# controlo_rev3.net
KiCad netlist of a schematic drawn in Altium Designer
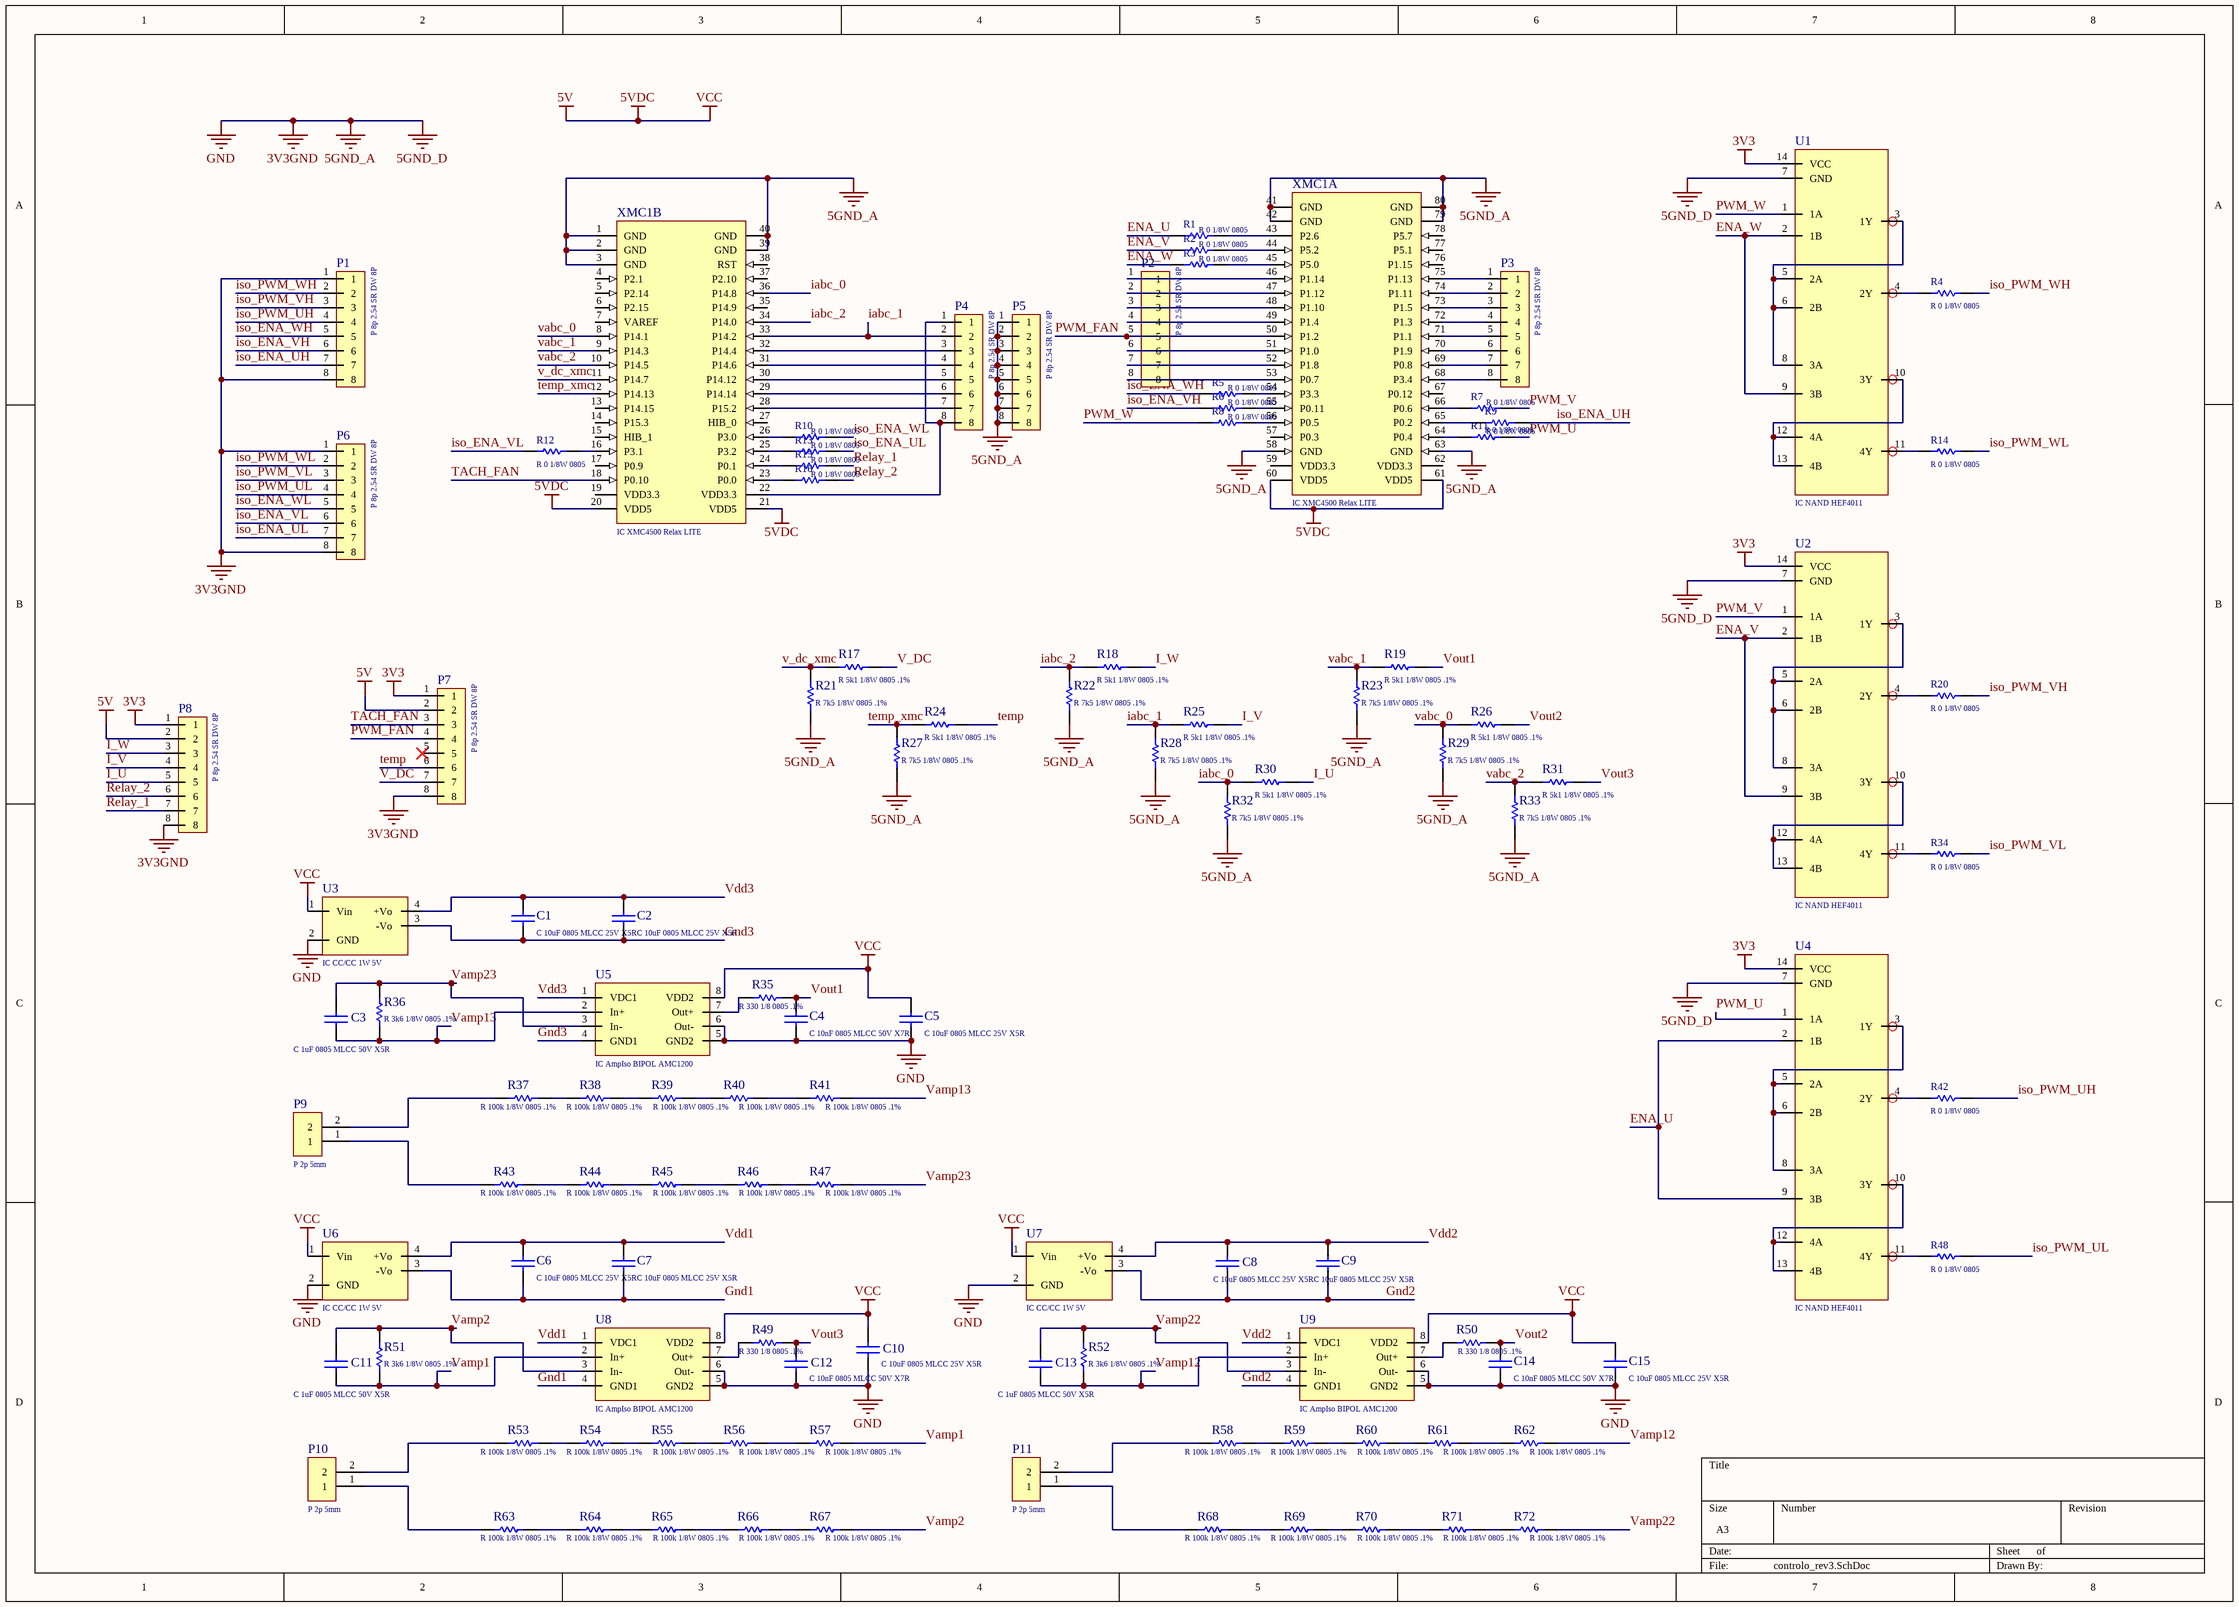
[diagram p0: controlo_rev3.SchDoc]

(export (version "E")
  (design (tool "Eeschema 10.0.6"))
  (components
    (comp (ref "C1")
      (value "C 10uF 0805 MLCC 25V X5R")
      (footprint "CAPC_0805")
      (description "Capacitores de cerâmica multicamada MLCC - SMD/SMT 10uF 25V X5R +/-10% 0805 Gen Purp")
      (libsource (lib "vi_measurement") (part "Capacitor SMD"))
    )
    (comp (ref "C2")
      (value "C 10uF 0805 MLCC 25V X5R")
      (footprint "CAPC_0805")
      (description "Capacitores de cerâmica multicamada MLCC - SMD/SMT 10uF 25V X5R +/-10% 0805 Gen Purp")
      (libsource (lib "vi_measurement") (part "Capacitor SMD"))
    )
    (comp (ref "C3")
      (value "C 1uF 0805 MLCC 50V X5R")
      (footprint "CAPC_0805")
      (description "Capacitores de cerâmica multicamada MLCC - SMD/SMT 0805 50V 1uF 20% X5R")
      (libsource (lib "vi_measurement") (part "Capacitor SMD"))
    )
    (comp (ref "C4")
      (value "C 10nF 0805 MLCC 50V X7R")
      (footprint "CAPC_0805")
      (description "Capacitores de cerâmica multicamada MLCC - SMD/SMT 10nF 50V X7R 10%")
      (libsource (lib "vi_measurement") (part "Capacitor SMD"))
    )
    (comp (ref "C5")
      (value "C 10uF 0805 MLCC 25V X5R")
      (footprint "CAPC_0805")
      (description "Capacitores de cerâmica multicamada MLCC - SMD/SMT 10uF 25V X5R +/-10% 0805 Gen Purp")
      (libsource (lib "vi_measurement") (part "Capacitor SMD"))
    )
    (comp (ref "C6")
      (value "C 10uF 0805 MLCC 25V X5R")
      (footprint "CAPC_0805")
      (description "Capacitores de cerâmica multicamada MLCC - SMD/SMT 10uF 25V X5R +/-10% 0805 Gen Purp")
      (libsource (lib "vi_measurement") (part "Capacitor SMD"))
    )
    (comp (ref "C7")
      (value "C 10uF 0805 MLCC 25V X5R")
      (footprint "CAPC_0805")
      (description "Capacitores de cerâmica multicamada MLCC - SMD/SMT 10uF 25V X5R +/-10% 0805 Gen Purp")
      (libsource (lib "vi_measurement") (part "Capacitor SMD"))
    )
    (comp (ref "C8")
      (value "C 10uF 0805 MLCC 25V X5R")
      (footprint "CAPC_0805")
      (description "Capacitores de cerâmica multicamada MLCC - SMD/SMT 10uF 25V X5R +/-10% 0805 Gen Purp")
      (libsource (lib "vi_measurement") (part "Capacitor SMD"))
    )
    (comp (ref "C9")
      (value "C 10uF 0805 MLCC 25V X5R")
      (footprint "CAPC_0805")
      (description "Capacitores de cerâmica multicamada MLCC - SMD/SMT 10uF 25V X5R +/-10% 0805 Gen Purp")
      (libsource (lib "vi_measurement") (part "Capacitor SMD"))
    )
    (comp (ref "C10")
      (value "C 10uF 0805 MLCC 25V X5R")
      (footprint "CAPC_0805")
      (description "Capacitores de cerâmica multicamada MLCC - SMD/SMT 10uF 25V X5R +/-10% 0805 Gen Purp")
      (libsource (lib "vi_measurement") (part "Capacitor SMD"))
    )
    (comp (ref "C11")
      (value "C 1uF 0805 MLCC 50V X5R")
      (footprint "CAPC_0805")
      (description "Capacitores de cerâmica multicamada MLCC - SMD/SMT 0805 50V 1uF 20% X5R")
      (libsource (lib "vi_measurement") (part "Capacitor SMD"))
    )
    (comp (ref "C12")
      (value "C 10nF 0805 MLCC 50V X7R")
      (footprint "CAPC_0805")
      (description "Capacitores de cerâmica multicamada MLCC - SMD/SMT 10nF 50V X7R 10%")
      (libsource (lib "vi_measurement") (part "Capacitor SMD"))
    )
    (comp (ref "C13")
      (value "C 1uF 0805 MLCC 50V X5R")
      (footprint "CAPC_0805")
      (description "Capacitores de cerâmica multicamada MLCC - SMD/SMT 0805 50V 1uF 20% X5R")
      (libsource (lib "vi_measurement") (part "Capacitor SMD"))
    )
    (comp (ref "C14")
      (value "C 10nF 0805 MLCC 50V X7R")
      (footprint "CAPC_0805")
      (description "Capacitores de cerâmica multicamada MLCC - SMD/SMT 10nF 50V X7R 10%")
      (libsource (lib "vi_measurement") (part "Capacitor SMD"))
    )
    (comp (ref "C15")
      (value "C 10uF 0805 MLCC 25V X5R")
      (footprint "CAPC_0805")
      (description "Capacitores de cerâmica multicamada MLCC - SMD/SMT 10uF 25V X5R +/-10% 0805 Gen Purp")
      (libsource (lib "vi_measurement") (part "Capacitor SMD"))
    )
    (comp (ref "P1")
      (value "P 8p 2.54 SR DW 8P")
      (footprint "Header 8x1 8.5mm")
      (description "Distribuidores e Alojamento de Fios CGrid Hrd SRDW THo le 8ckt")
      (libsource (lib "vmorais_libraries") (part "jumper_8p"))
    )
    (comp (ref "P2")
      (value "P 8p 2.54 SR DW 8P")
      (footprint "Header 8x1 8.5mm")
      (description "Distribuidores e Alojamento de Fios CGrid Hrd SRDW THo le 8ckt")
      (libsource (lib "vmorais_libraries") (part "jumper_8p"))
    )
    (comp (ref "P3")
      (value "P 8p 2.54 SR DW 8P")
      (footprint "Header 8x1 8.5mm")
      (description "Distribuidores e Alojamento de Fios CGrid Hrd SRDW THo le 8ckt")
      (libsource (lib "vmorais_libraries") (part "jumper_8p"))
    )
    (comp (ref "P4")
      (value "P 8p 2.54 SR DW 8P")
      (footprint "Header 8x1 8.5mm")
      (description "Distribuidores e Alojamento de Fios CGrid Hrd SRDW THo le 8ckt")
      (libsource (lib "vmorais_libraries") (part "jumper_8p"))
    )
    (comp (ref "P5")
      (value "P 8p 2.54 SR DW 8P")
      (footprint "Header 8x1 8.5mm")
      (description "Distribuidores e Alojamento de Fios CGrid Hrd SRDW THo le 8ckt")
      (libsource (lib "vmorais_libraries") (part "jumper_8p"))
    )
    (comp (ref "P6")
      (value "P 8p 2.54 SR DW 8P")
      (footprint "Header 8x1 8.5mm")
      (description "Distribuidores e Alojamento de Fios CGrid Hrd SRDW THo le 8ckt")
      (libsource (lib "vmorais_libraries") (part "jumper_8p"))
    )
    (comp (ref "P7")
      (value "P 8p 2.54 SR DW 8P")
      (footprint "Header 8x1 8.5mm")
      (description "Distribuidores e Alojamento de Fios CGrid Hrd SRDW THo le 8ckt")
      (libsource (lib "vmorais_libraries") (part "jumper_8p"))
    )
    (comp (ref "P8")
      (value "P 8p 2.54 SR DW 8P")
      (footprint "Header 8x1 8.5mm")
      (description "Distribuidores e Alojamento de Fios CGrid Hrd SRDW THo le 8ckt")
      (libsource (lib "vmorais_libraries") (part "jumper_8p"))
    )
    (comp (ref "P9")
      (value "P 2p 5mm")
      (footprint "connector1x2_parafuso")
      (description "Bloques de terminales de PCB de perfil estándar RS de 5,0 mm")
      (libsource (lib "malvega_pcb") (part "gen_purpose_conn_1x2"))
    )
    (comp (ref "P10")
      (value "P 2p 5mm")
      (footprint "connector1x2_parafuso")
      (description "Bloques de terminales de PCB de perfil estándar RS de 5,0 mm")
      (libsource (lib "malvega_pcb") (part "gen_purpose_conn_1x2"))
    )
    (comp (ref "P11")
      (value "P 2p 5mm")
      (footprint "connector1x2_parafuso")
      (description "Bloques de terminales de PCB de perfil estándar RS de 5,0 mm")
      (libsource (lib "malvega_pcb") (part "gen_purpose_conn_1x2"))
    )
    (comp (ref "R1")
      (value "R 0 1/8W 0805")
      (footprint "RESC_0805")
      (description "Resistores de Filme Espesso - SMD 1/8Watt 0ohms Commercial Use")
      (libsource (lib "inversor_50a") (part "Resistor"))
    )
    (comp (ref "R2")
      (value "R 0 1/8W 0805")
      (footprint "RESC_0805")
      (description "Resistores de Filme Espesso - SMD 1/8Watt 0ohms Commercial Use")
      (libsource (lib "inversor_50a") (part "Resistor"))
    )
    (comp (ref "R3")
      (value "R 0 1/8W 0805")
      (footprint "RESC_0805")
      (description "Resistores de Filme Espesso - SMD 1/8Watt 0ohms Commercial Use")
      (libsource (lib "inversor_50a") (part "Resistor"))
    )
    (comp (ref "R4")
      (value "R 0 1/8W 0805")
      (footprint "RESC_0805")
      (description "Resistores de Filme Espesso - SMD 1/8Watt 0ohms Commercial Use")
      (libsource (lib "inversor_50a") (part "Resistor"))
    )
    (comp (ref "R5")
      (value "R 0 1/8W 0805")
      (footprint "RESC_0805")
      (description "Resistores de Filme Espesso - SMD 1/8Watt 0ohms Commercial Use")
      (libsource (lib "inversor_50a") (part "Resistor"))
    )
    (comp (ref "R6")
      (value "R 0 1/8W 0805")
      (footprint "RESC_0805")
      (description "Resistores de Filme Espesso - SMD 1/8Watt 0ohms Commercial Use")
      (libsource (lib "inversor_50a") (part "Resistor"))
    )
    (comp (ref "R7")
      (value "R 0 1/8W 0805")
      (footprint "RESC_0805")
      (description "Resistores de Filme Espesso - SMD 1/8Watt 0ohms Commercial Use")
      (libsource (lib "inversor_50a") (part "Resistor"))
    )
    (comp (ref "R8")
      (value "R 0 1/8W 0805")
      (footprint "RESC_0805")
      (description "Resistores de Filme Espesso - SMD 1/8Watt 0ohms Commercial Use")
      (libsource (lib "inversor_50a") (part "Resistor"))
    )
    (comp (ref "R9")
      (value "R 0 1/8W 0805")
      (footprint "RESC_0805")
      (description "Resistores de Filme Espesso - SMD 1/8Watt 0ohms Commercial Use")
      (libsource (lib "inversor_50a") (part "Resistor"))
    )
    (comp (ref "R10")
      (value "R 0 1/8W 0805")
      (footprint "RESC_0805")
      (description "Resistores de Filme Espesso - SMD 1/8Watt 0ohms Commercial Use")
      (libsource (lib "inversor_50a") (part "Resistor"))
    )
    (comp (ref "R11")
      (value "R 0 1/8W 0805")
      (footprint "RESC_0805")
      (description "Resistores de Filme Espesso - SMD 1/8Watt 0ohms Commercial Use")
      (libsource (lib "inversor_50a") (part "Resistor"))
    )
    (comp (ref "R12")
      (value "R 0 1/8W 0805")
      (footprint "RESC_0805")
      (description "Resistores de Filme Espesso - SMD 1/8Watt 0ohms Commercial Use")
      (libsource (lib "inversor_50a") (part "Resistor"))
    )
    (comp (ref "R13")
      (value "R 0 1/8W 0805")
      (footprint "RESC_0805")
      (description "Resistores de Filme Espesso - SMD 1/8Watt 0ohms Commercial Use")
      (libsource (lib "inversor_50a") (part "Resistor"))
    )
    (comp (ref "R14")
      (value "R 0 1/8W 0805")
      (footprint "RESC_0805")
      (description "Resistores de Filme Espesso - SMD 1/8Watt 0ohms Commercial Use")
      (libsource (lib "inversor_50a") (part "Resistor"))
    )
    (comp (ref "R15")
      (value "R 0 1/8W 0805")
      (footprint "RESC_0805")
      (description "Resistores de Filme Espesso - SMD 1/8Watt 0ohms Commercial Use")
      (libsource (lib "inversor_50a") (part "Resistor"))
    )
    (comp (ref "R16")
      (value "R 0 1/8W 0805")
      (footprint "RESC_0805")
      (description "Resistores de Filme Espesso - SMD 1/8Watt 0ohms Commercial Use")
      (libsource (lib "inversor_50a") (part "Resistor"))
    )
    (comp (ref "R17")
      (value "R 5k1 1/8W 0805 .1%")
      (footprint "RESC_0805")
      (description "Resistores de Filme Fino - SMD 0805 5.1Kohm 1/8W .1% 25ppm")
      (libsource (lib "inversor_50a") (part "Resistor"))
    )
    (comp (ref "R18")
      (value "R 5k1 1/8W 0805 .1%")
      (footprint "RESC_0805")
      (description "Resistores de Filme Fino - SMD 0805 5.1Kohm 1/8W .1% 25ppm")
      (libsource (lib "inversor_50a") (part "Resistor"))
    )
    (comp (ref "R19")
      (value "R 5k1 1/8W 0805 .1%")
      (footprint "RESC_0805")
      (description "Resistores de Filme Fino - SMD 0805 5.1Kohm 1/8W .1% 25ppm")
      (libsource (lib "inversor_50a") (part "Resistor"))
    )
    (comp (ref "R20")
      (value "R 0 1/8W 0805")
      (footprint "RESC_0805")
      (description "Resistores de Filme Espesso - SMD 1/8Watt 0ohms Commercial Use")
      (libsource (lib "inversor_50a") (part "Resistor"))
    )
    (comp (ref "R21")
      (value "R 7k5 1/8W 0805 .1%")
      (footprint "RESC_0805")
      (description "Resistores de Filme Fino - SMD 7.5K OHM .1% 25ppm")
      (libsource (lib "inversor_50a") (part "Resistor"))
    )
    (comp (ref "R22")
      (value "R 7k5 1/8W 0805 .1%")
      (footprint "RESC_0805")
      (description "Resistores de Filme Fino - SMD 7.5K OHM .1% 25ppm")
      (libsource (lib "inversor_50a") (part "Resistor"))
    )
    (comp (ref "R23")
      (value "R 7k5 1/8W 0805 .1%")
      (footprint "RESC_0805")
      (description "Resistores de Filme Fino - SMD 7.5K OHM .1% 25ppm")
      (libsource (lib "inversor_50a") (part "Resistor"))
    )
    (comp (ref "R24")
      (value "R 5k1 1/8W 0805 .1%")
      (footprint "RESC_0805")
      (description "Resistores de Filme Fino - SMD 0805 5.1Kohm 1/8W .1% 25ppm")
      (libsource (lib "inversor_50a") (part "Resistor"))
    )
    (comp (ref "R25")
      (value "R 5k1 1/8W 0805 .1%")
      (footprint "RESC_0805")
      (description "Resistores de Filme Fino - SMD 0805 5.1Kohm 1/8W .1% 25ppm")
      (libsource (lib "inversor_50a") (part "Resistor"))
    )
    (comp (ref "R26")
      (value "R 5k1 1/8W 0805 .1%")
      (footprint "RESC_0805")
      (description "Resistores de Filme Fino - SMD 0805 5.1Kohm 1/8W .1% 25ppm")
      (libsource (lib "inversor_50a") (part "Resistor"))
    )
    (comp (ref "R27")
      (value "R 7k5 1/8W 0805 .1%")
      (footprint "RESC_0805")
      (description "Resistores de Filme Fino - SMD 7.5K OHM .1% 25ppm")
      (libsource (lib "inversor_50a") (part "Resistor"))
    )
    (comp (ref "R28")
      (value "R 7k5 1/8W 0805 .1%")
      (footprint "RESC_0805")
      (description "Resistores de Filme Fino - SMD 7.5K OHM .1% 25ppm")
      (libsource (lib "inversor_50a") (part "Resistor"))
    )
    (comp (ref "R29")
      (value "R 7k5 1/8W 0805 .1%")
      (footprint "RESC_0805")
      (description "Resistores de Filme Fino - SMD 7.5K OHM .1% 25ppm")
      (libsource (lib "inversor_50a") (part "Resistor"))
    )
    (comp (ref "R30")
      (value "R 5k1 1/8W 0805 .1%")
      (footprint "RESC_0805")
      (description "Resistores de Filme Fino - SMD 0805 5.1Kohm 1/8W .1% 25ppm")
      (libsource (lib "inversor_50a") (part "Resistor"))
    )
    (comp (ref "R31")
      (value "R 5k1 1/8W 0805 .1%")
      (footprint "RESC_0805")
      (description "Resistores de Filme Fino - SMD 0805 5.1Kohm 1/8W .1% 25ppm")
      (libsource (lib "inversor_50a") (part "Resistor"))
    )
    (comp (ref "R32")
      (value "R 7k5 1/8W 0805 .1%")
      (footprint "RESC_0805")
      (description "Resistores de Filme Fino - SMD 7.5K OHM .1% 25ppm")
      (libsource (lib "inversor_50a") (part "Resistor"))
    )
    (comp (ref "R33")
      (value "R 7k5 1/8W 0805 .1%")
      (footprint "RESC_0805")
      (description "Resistores de Filme Fino - SMD 7.5K OHM .1% 25ppm")
      (libsource (lib "inversor_50a") (part "Resistor"))
    )
    (comp (ref "R34")
      (value "R 0 1/8W 0805")
      (footprint "RESC_0805")
      (description "Resistores de Filme Espesso - SMD 1/8Watt 0ohms Commercial Use")
      (libsource (lib "inversor_50a") (part "Resistor"))
    )
    (comp (ref "R35")
      (value "R 330 1/8 0805 .1%")
      (footprint "RESC_0805")
      (description "Resistores de Filme Fino - SMD CPF 0805 330R 0.1% 25PPM 1K RL")
      (libsource (lib "inversor_50a") (part "Resistor"))
    )
    (comp (ref "R36")
      (value "R 3k6 1/8W 0805 .1%")
      (footprint "RESC_0805")
      (description "Resistores de Filme Fino - SMD 1/8W 3.6K ohm .1% 25ppm")
      (libsource (lib "inversor_50a") (part "Resistor"))
    )
    (comp (ref "R37")
      (value "R 100k 1/8W 0805 .1%")
      (footprint "RESC_0805")
      (description "Resistores de Filme Fino - SMD 100 Kohm .1% 0805 25PPM")
      (libsource (lib "inversor_50a") (part "Resistor"))
    )
    (comp (ref "R38")
      (value "R 100k 1/8W 0805 .1%")
      (footprint "RESC_0805")
      (description "Resistores de Filme Fino - SMD 100 Kohm .1% 0805 25PPM")
      (libsource (lib "inversor_50a") (part "Resistor"))
    )
    (comp (ref "R39")
      (value "R 100k 1/8W 0805 .1%")
      (footprint "RESC_0805")
      (description "Resistores de Filme Fino - SMD 100 Kohm .1% 0805 25PPM")
      (libsource (lib "inversor_50a") (part "Resistor"))
    )
    (comp (ref "R40")
      (value "R 100k 1/8W 0805 .1%")
      (footprint "RESC_0805")
      (description "Resistores de Filme Fino - SMD 100 Kohm .1% 0805 25PPM")
      (libsource (lib "inversor_50a") (part "Resistor"))
    )
    (comp (ref "R41")
      (value "R 100k 1/8W 0805 .1%")
      (footprint "RESC_0805")
      (description "Resistores de Filme Fino - SMD 100 Kohm .1% 0805 25PPM")
      (libsource (lib "inversor_50a") (part "Resistor"))
    )
    (comp (ref "R42")
      (value "R 0 1/8W 0805")
      (footprint "RESC_0805")
      (description "Resistores de Filme Espesso - SMD 1/8Watt 0ohms Commercial Use")
      (libsource (lib "inversor_50a") (part "Resistor"))
    )
    (comp (ref "R43")
      (value "R 100k 1/8W 0805 .1%")
      (footprint "RESC_0805")
      (description "Resistores de Filme Fino - SMD 100 Kohm .1% 0805 25PPM")
      (libsource (lib "inversor_50a") (part "Resistor"))
    )
    (comp (ref "R44")
      (value "R 100k 1/8W 0805 .1%")
      (footprint "RESC_0805")
      (description "Resistores de Filme Fino - SMD 100 Kohm .1% 0805 25PPM")
      (libsource (lib "inversor_50a") (part "Resistor"))
    )
    (comp (ref "R45")
      (value "R 100k 1/8W 0805 .1%")
      (footprint "RESC_0805")
      (description "Resistores de Filme Fino - SMD 100 Kohm .1% 0805 25PPM")
      (libsource (lib "inversor_50a") (part "Resistor"))
    )
    (comp (ref "R46")
      (value "R 100k 1/8W 0805 .1%")
      (footprint "RESC_0805")
      (description "Resistores de Filme Fino - SMD 100 Kohm .1% 0805 25PPM")
      (libsource (lib "inversor_50a") (part "Resistor"))
    )
    (comp (ref "R47")
      (value "R 100k 1/8W 0805 .1%")
      (footprint "RESC_0805")
      (description "Resistores de Filme Fino - SMD 100 Kohm .1% 0805 25PPM")
      (libsource (lib "inversor_50a") (part "Resistor"))
    )
    (comp (ref "R48")
      (value "R 0 1/8W 0805")
      (footprint "RESC_0805")
      (description "Resistores de Filme Espesso - SMD 1/8Watt 0ohms Commercial Use")
      (libsource (lib "inversor_50a") (part "Resistor"))
    )
    (comp (ref "R49")
      (value "R 330 1/8 0805 .1%")
      (footprint "RESC_0805")
      (description "Resistores de Filme Fino - SMD CPF 0805 330R 0.1% 25PPM 1K RL")
      (libsource (lib "inversor_50a") (part "Resistor"))
    )
    (comp (ref "R50")
      (value "R 330 1/8 0805 .1%")
      (footprint "RESC_0805")
      (description "Resistores de Filme Fino - SMD CPF 0805 330R 0.1% 25PPM 1K RL")
      (libsource (lib "inversor_50a") (part "Resistor"))
    )
    (comp (ref "R51")
      (value "R 3k6 1/8W 0805 .1%")
      (footprint "RESC_0805")
      (description "Resistores de Filme Fino - SMD 1/8W 3.6K ohm .1% 25ppm")
      (libsource (lib "inversor_50a") (part "Resistor"))
    )
    (comp (ref "R52")
      (value "R 3k6 1/8W 0805 .1%")
      (footprint "RESC_0805")
      (description "Resistores de Filme Fino - SMD 1/8W 3.6K ohm .1% 25ppm")
      (libsource (lib "inversor_50a") (part "Resistor"))
    )
    (comp (ref "R53")
      (value "R 100k 1/8W 0805 .1%")
      (footprint "RESC_0805")
      (description "Resistores de Filme Fino - SMD 100 Kohm .1% 0805 25PPM")
      (libsource (lib "inversor_50a") (part "Resistor"))
    )
    (comp (ref "R54")
      (value "R 100k 1/8W 0805 .1%")
      (footprint "RESC_0805")
      (description "Resistores de Filme Fino - SMD 100 Kohm .1% 0805 25PPM")
      (libsource (lib "inversor_50a") (part "Resistor"))
    )
    (comp (ref "R55")
      (value "R 100k 1/8W 0805 .1%")
      (footprint "RESC_0805")
      (description "Resistores de Filme Fino - SMD 100 Kohm .1% 0805 25PPM")
      (libsource (lib "inversor_50a") (part "Resistor"))
    )
    (comp (ref "R56")
      (value "R 100k 1/8W 0805 .1%")
      (footprint "RESC_0805")
      (description "Resistores de Filme Fino - SMD 100 Kohm .1% 0805 25PPM")
      (libsource (lib "inversor_50a") (part "Resistor"))
    )
    (comp (ref "R57")
      (value "R 100k 1/8W 0805 .1%")
      (footprint "RESC_0805")
      (description "Resistores de Filme Fino - SMD 100 Kohm .1% 0805 25PPM")
      (libsource (lib "inversor_50a") (part "Resistor"))
    )
    (comp (ref "R58")
      (value "R 100k 1/8W 0805 .1%")
      (footprint "RESC_0805")
      (description "Resistores de Filme Fino - SMD 100 Kohm .1% 0805 25PPM")
      (libsource (lib "inversor_50a") (part "Resistor"))
    )
    (comp (ref "R59")
      (value "R 100k 1/8W 0805 .1%")
      (footprint "RESC_0805")
      (description "Resistores de Filme Fino - SMD 100 Kohm .1% 0805 25PPM")
      (libsource (lib "inversor_50a") (part "Resistor"))
    )
    (comp (ref "R60")
      (value "R 100k 1/8W 0805 .1%")
      (footprint "RESC_0805")
      (description "Resistores de Filme Fino - SMD 100 Kohm .1% 0805 25PPM")
      (libsource (lib "inversor_50a") (part "Resistor"))
    )
    (comp (ref "R61")
      (value "R 100k 1/8W 0805 .1%")
      (footprint "RESC_0805")
      (description "Resistores de Filme Fino - SMD 100 Kohm .1% 0805 25PPM")
      (libsource (lib "inversor_50a") (part "Resistor"))
    )
    (comp (ref "R62")
      (value "R 100k 1/8W 0805 .1%")
      (footprint "RESC_0805")
      (description "Resistores de Filme Fino - SMD 100 Kohm .1% 0805 25PPM")
      (libsource (lib "inversor_50a") (part "Resistor"))
    )
    (comp (ref "R63")
      (value "R 100k 1/8W 0805 .1%")
      (footprint "RESC_0805")
      (description "Resistores de Filme Fino - SMD 100 Kohm .1% 0805 25PPM")
      (libsource (lib "inversor_50a") (part "Resistor"))
    )
    (comp (ref "R64")
      (value "R 100k 1/8W 0805 .1%")
      (footprint "RESC_0805")
      (description "Resistores de Filme Fino - SMD 100 Kohm .1% 0805 25PPM")
      (libsource (lib "inversor_50a") (part "Resistor"))
    )
    (comp (ref "R65")
      (value "R 100k 1/8W 0805 .1%")
      (footprint "RESC_0805")
      (description "Resistores de Filme Fino - SMD 100 Kohm .1% 0805 25PPM")
      (libsource (lib "inversor_50a") (part "Resistor"))
    )
    (comp (ref "R66")
      (value "R 100k 1/8W 0805 .1%")
      (footprint "RESC_0805")
      (description "Resistores de Filme Fino - SMD 100 Kohm .1% 0805 25PPM")
      (libsource (lib "inversor_50a") (part "Resistor"))
    )
    (comp (ref "R67")
      (value "R 100k 1/8W 0805 .1%")
      (footprint "RESC_0805")
      (description "Resistores de Filme Fino - SMD 100 Kohm .1% 0805 25PPM")
      (libsource (lib "inversor_50a") (part "Resistor"))
    )
    (comp (ref "R68")
      (value "R 100k 1/8W 0805 .1%")
      (footprint "RESC_0805")
      (description "Resistores de Filme Fino - SMD 100 Kohm .1% 0805 25PPM")
      (libsource (lib "inversor_50a") (part "Resistor"))
    )
    (comp (ref "R69")
      (value "R 100k 1/8W 0805 .1%")
      (footprint "RESC_0805")
      (description "Resistores de Filme Fino - SMD 100 Kohm .1% 0805 25PPM")
      (libsource (lib "inversor_50a") (part "Resistor"))
    )
    (comp (ref "R70")
      (value "R 100k 1/8W 0805 .1%")
      (footprint "RESC_0805")
      (description "Resistores de Filme Fino - SMD 100 Kohm .1% 0805 25PPM")
      (libsource (lib "inversor_50a") (part "Resistor"))
    )
    (comp (ref "R71")
      (value "R 100k 1/8W 0805 .1%")
      (footprint "RESC_0805")
      (description "Resistores de Filme Fino - SMD 100 Kohm .1% 0805 25PPM")
      (libsource (lib "inversor_50a") (part "Resistor"))
    )
    (comp (ref "R72")
      (value "R 100k 1/8W 0805 .1%")
      (footprint "RESC_0805")
      (description "Resistores de Filme Fino - SMD 100 Kohm .1% 0805 25PPM")
      (libsource (lib "inversor_50a") (part "Resistor"))
    )
    (comp (ref "U1")
      (value "IC NAND HEF4011")
      (footprint "SOIC-14N")
      (description "Portas lógicas QUADRUPLE 2-INPUT NAND GATE")
      (libsource (lib "vmorais_libraries") (part "HEF4011"))
    )
    (comp (ref "U2")
      (value "IC NAND HEF4011")
      (footprint "SOIC-14N")
      (description "Portas lógicas QUADRUPLE 2-INPUT NAND GATE")
      (libsource (lib "vmorais_libraries") (part "HEF4011"))
    )
    (comp (ref "U3")
      (value "IC CC/CC 1W 5V")
      (footprint "DC/DC_ISO")
      (description "Conversores CC/CC com isolação 1W 5Vin 5Vout 200mA SIP7")
      (libsource (lib "vi_measurement") (part "DC/DC_ISO"))
    )
    (comp (ref "U4")
      (value "IC NAND HEF4011")
      (footprint "SOIC-14N")
      (description "Portas lógicas QUADRUPLE 2-INPUT NAND GATE")
      (libsource (lib "vmorais_libraries") (part "HEF4011"))
    )
    (comp (ref "U5")
      (value "IC AmpIso BIPOL AMC1200")
      (footprint "SOIC8")
      (description "Amplificadores de isolamento 4kV peak Iso Amp")
      (libsource (lib "vi_measurement") (part "AMC1200"))
    )
    (comp (ref "U6")
      (value "IC CC/CC 1W 5V")
      (footprint "DC/DC_ISO")
      (description "Conversores CC/CC com isolação 1W 5Vin 5Vout 200mA SIP7")
      (libsource (lib "vi_measurement") (part "DC/DC_ISO"))
    )
    (comp (ref "U7")
      (value "IC CC/CC 1W 5V")
      (footprint "DC/DC_ISO")
      (description "Conversores CC/CC com isolação 1W 5Vin 5Vout 200mA SIP7")
      (libsource (lib "vi_measurement") (part "DC/DC_ISO"))
    )
    (comp (ref "U8")
      (value "IC AmpIso BIPOL AMC1200")
      (footprint "SOIC8")
      (description "Amplificadores de isolamento 4kV peak Iso Amp")
      (libsource (lib "vi_measurement") (part "AMC1200"))
    )
    (comp (ref "U9")
      (value "IC AmpIso BIPOL AMC1200")
      (footprint "SOIC8")
      (description "Amplificadores de isolamento 4kV peak Iso Amp")
      (libsource (lib "vi_measurement") (part "AMC1200"))
    )
    (comp (ref "XMC1")
      (value "IC XMC4500 Relax LITE")
      (footprint "XMC4500")
      (libsource (lib "vmorais_libraries") (part "XMC4500"))
    )
  )
  (nets
    (net (code "1") (name "/ENA_U") (class "Default")
      (node (ref "R1") (pin "1") (pinfunction "1_1") (pintype "passive"))
      (node (ref "U4") (pin "2") (pinfunction "1B_2") (pintype "passive"))
      (node (ref "U4") (pin "9") (pinfunction "3B_9") (pintype "passive"))
    )
    (net (code "2") (name "/ENA_V") (class "Default")
      (node (ref "R2") (pin "1") (pinfunction "1_1") (pintype "passive"))
      (node (ref "U2") (pin "2") (pinfunction "1B_2") (pintype "passive"))
      (node (ref "U2") (pin "9") (pinfunction "3B_9") (pintype "passive"))
    )
    (net (code "3") (name "/ENA_W") (class "Default")
      (node (ref "R3") (pin "1") (pinfunction "1_1") (pintype "passive"))
      (node (ref "U1") (pin "2") (pinfunction "1B_2") (pintype "passive"))
      (node (ref "U1") (pin "9") (pinfunction "3B_9") (pintype "passive"))
    )
    (net (code "4") (name "/Gnd1") (class "Default")
      (node (ref "C6") (pin "1") (pinfunction "1_1") (pintype "passive"))
      (node (ref "C7") (pin "1") (pinfunction "1_1") (pintype "passive"))
      (node (ref "U6") (pin "3") (pinfunction "-Vo_3") (pintype "passive"))
      (node (ref "U8") (pin "4") (pinfunction "GND1_4") (pintype "passive"))
    )
    (net (code "5") (name "/Gnd2") (class "Default")
      (node (ref "C8") (pin "1") (pinfunction "1_1") (pintype "passive"))
      (node (ref "C9") (pin "1") (pinfunction "1_1") (pintype "passive"))
      (node (ref "U7") (pin "3") (pinfunction "-Vo_3") (pintype "passive"))
      (node (ref "U9") (pin "4") (pinfunction "GND1_4") (pintype "passive"))
    )
    (net (code "6") (name "/Gnd3") (class "Default")
      (node (ref "C1") (pin "1") (pinfunction "1_1") (pintype "passive"))
      (node (ref "C2") (pin "1") (pinfunction "1_1") (pintype "passive"))
      (node (ref "U3") (pin "3") (pinfunction "-Vo_3") (pintype "passive"))
      (node (ref "U5") (pin "4") (pinfunction "GND1_4") (pintype "passive"))
    )
    (net (code "7") (name "/I_U") (class "Default")
      (node (ref "P8") (pin "5") (pinfunction "5_5") (pintype "passive"))
      (node (ref "R30") (pin "2") (pinfunction "2_2") (pintype "passive"))
    )
    (net (code "8") (name "/I_V") (class "Default")
      (node (ref "P8") (pin "4") (pinfunction "4_4") (pintype "passive"))
      (node (ref "R25") (pin "2") (pinfunction "2_2") (pintype "passive"))
    )
    (net (code "9") (name "/I_W") (class "Default")
      (node (ref "P8") (pin "3") (pinfunction "3_3") (pintype "passive"))
      (node (ref "R18") (pin "2") (pinfunction "2_2") (pintype "passive"))
    )
    (net (code "10") (name "/PWM_FAN") (class "Default")
      (node (ref "P2") (pin "5") (pinfunction "5_5") (pintype "passive"))
      (node (ref "P7") (pin "4") (pinfunction "4_4") (pintype "passive"))
      (node (ref "XMC1") (pin "50") (pinfunction "P1.2_50") (pintype "input"))
    )
    (net (code "11") (name "/PWM_U") (class "Default")
      (node (ref "R11") (pin "2") (pinfunction "2_2") (pintype "passive"))
      (node (ref "U4") (pin "1") (pinfunction "1A_1") (pintype "passive"))
    )
    (net (code "12") (name "/PWM_V") (class "Default")
      (node (ref "R7") (pin "2") (pinfunction "2_2") (pintype "passive"))
      (node (ref "U2") (pin "1") (pinfunction "1A_1") (pintype "passive"))
    )
    (net (code "13") (name "/PWM_W") (class "Default")
      (node (ref "R8") (pin "1") (pinfunction "1_1") (pintype "passive"))
      (node (ref "U1") (pin "1") (pinfunction "1A_1") (pintype "passive"))
    )
    (net (code "14") (name "/Relay_1") (class "Default")
      (node (ref "P8") (pin "7") (pinfunction "7_7") (pintype "passive"))
      (node (ref "R15") (pin "2") (pinfunction "2_2") (pintype "passive"))
    )
    (net (code "15") (name "/Relay_2") (class "Default")
      (node (ref "P8") (pin "6") (pinfunction "6_6") (pintype "passive"))
      (node (ref "R16") (pin "2") (pinfunction "2_2") (pintype "passive"))
    )
    (net (code "16") (name "/TACH_FAN") (class "Default")
      (node (ref "P7") (pin "3") (pinfunction "3_3") (pintype "passive"))
      (node (ref "XMC1") (pin "18") (pinfunction "P0.10_18") (pintype "input"))
    )
    (net (code "17") (name "/V_DC") (class "Default")
      (node (ref "P7") (pin "7") (pinfunction "7_7") (pintype "passive"))
      (node (ref "R17") (pin "2") (pinfunction "2_2") (pintype "passive"))
    )
    (net (code "18") (name "/Vamp1") (class "Default")
      (node (ref "C11") (pin "1") (pinfunction "1_1") (pintype "passive"))
      (node (ref "R51") (pin "1") (pinfunction "1_1") (pintype "passive"))
      (node (ref "R57") (pin "2") (pinfunction "2_2") (pintype "passive"))
      (node (ref "U8") (pin "2") (pinfunction "In+_2") (pintype "passive"))
    )
    (net (code "19") (name "/Vamp2") (class "Default")
      (node (ref "C11") (pin "2") (pinfunction "2_2") (pintype "passive"))
      (node (ref "R51") (pin "2") (pinfunction "2_2") (pintype "passive"))
      (node (ref "R67") (pin "2") (pinfunction "2_2") (pintype "passive"))
      (node (ref "U8") (pin "3") (pinfunction "In-_3") (pintype "passive"))
    )
    (net (code "20") (name "/Vamp12") (class "Default")
      (node (ref "C13") (pin "1") (pinfunction "1_1") (pintype "passive"))
      (node (ref "R52") (pin "1") (pinfunction "1_1") (pintype "passive"))
      (node (ref "R62") (pin "2") (pinfunction "2_2") (pintype "passive"))
      (node (ref "U9") (pin "2") (pinfunction "In+_2") (pintype "passive"))
    )
    (net (code "21") (name "/Vamp13") (class "Default")
      (node (ref "C3") (pin "1") (pinfunction "1_1") (pintype "passive"))
      (node (ref "R36") (pin "1") (pinfunction "1_1") (pintype "passive"))
      (node (ref "R41") (pin "2") (pinfunction "2_2") (pintype "passive"))
      (node (ref "U5") (pin "2") (pinfunction "In+_2") (pintype "passive"))
    )
    (net (code "22") (name "/Vamp22") (class "Default")
      (node (ref "C13") (pin "2") (pinfunction "2_2") (pintype "passive"))
      (node (ref "R52") (pin "2") (pinfunction "2_2") (pintype "passive"))
      (node (ref "R72") (pin "2") (pinfunction "2_2") (pintype "passive"))
      (node (ref "U9") (pin "3") (pinfunction "In-_3") (pintype "passive"))
    )
    (net (code "23") (name "/Vamp23") (class "Default")
      (node (ref "C3") (pin "2") (pinfunction "2_2") (pintype "passive"))
      (node (ref "R36") (pin "2") (pinfunction "2_2") (pintype "passive"))
      (node (ref "R47") (pin "2") (pinfunction "2_2") (pintype "passive"))
      (node (ref "U5") (pin "3") (pinfunction "In-_3") (pintype "passive"))
    )
    (net (code "24") (name "/Vdd1") (class "Default")
      (node (ref "C6") (pin "2") (pinfunction "2_2") (pintype "passive"))
      (node (ref "C7") (pin "2") (pinfunction "2_2") (pintype "passive"))
      (node (ref "U6") (pin "4") (pinfunction "+Vo_4") (pintype "passive"))
      (node (ref "U8") (pin "1") (pinfunction "VDC1_1") (pintype "passive"))
    )
    (net (code "25") (name "/Vdd2") (class "Default")
      (node (ref "C8") (pin "2") (pinfunction "2_2") (pintype "passive"))
      (node (ref "C9") (pin "2") (pinfunction "2_2") (pintype "passive"))
      (node (ref "U7") (pin "4") (pinfunction "+Vo_4") (pintype "passive"))
      (node (ref "U9") (pin "1") (pinfunction "VDC1_1") (pintype "passive"))
    )
    (net (code "26") (name "/Vdd3") (class "Default")
      (node (ref "C1") (pin "2") (pinfunction "2_2") (pintype "passive"))
      (node (ref "C2") (pin "2") (pinfunction "2_2") (pintype "passive"))
      (node (ref "U3") (pin "4") (pinfunction "+Vo_4") (pintype "passive"))
      (node (ref "U5") (pin "1") (pinfunction "VDC1_1") (pintype "passive"))
    )
    (net (code "27") (name "/Vout1") (class "Default")
      (node (ref "C4") (pin "2") (pinfunction "2_2") (pintype "passive"))
      (node (ref "R19") (pin "2") (pinfunction "2_2") (pintype "passive"))
      (node (ref "R35") (pin "2") (pinfunction "2_2") (pintype "passive"))
    )
    (net (code "28") (name "/Vout2") (class "Default")
      (node (ref "C14") (pin "2") (pinfunction "2_2") (pintype "passive"))
      (node (ref "R26") (pin "2") (pinfunction "2_2") (pintype "passive"))
      (node (ref "R50") (pin "2") (pinfunction "2_2") (pintype "passive"))
    )
    (net (code "29") (name "/Vout3") (class "Default")
      (node (ref "C12") (pin "2") (pinfunction "2_2") (pintype "passive"))
      (node (ref "R31") (pin "2") (pinfunction "2_2") (pintype "passive"))
      (node (ref "R49") (pin "2") (pinfunction "2_2") (pintype "passive"))
    )
    (net (code "30") (name "/iabc_0") (class "Default")
      (node (ref "R30") (pin "1") (pinfunction "1_1") (pintype "passive"))
      (node (ref "R32") (pin "2") (pinfunction "2_2") (pintype "passive"))
      (node (ref "XMC1") (pin "36") (pinfunction "P14.8_36") (pintype "input"))
    )
    (net (code "31") (name "/iabc_1") (class "Default")
      (node (ref "P4") (pin "2") (pinfunction "2_2") (pintype "passive"))
      (node (ref "R25") (pin "1") (pinfunction "1_1") (pintype "passive"))
      (node (ref "R28") (pin "2") (pinfunction "2_2") (pintype "passive"))
      (node (ref "XMC1") (pin "33") (pinfunction "P14.2_33") (pintype "input"))
    )
    (net (code "32") (name "/iabc_2") (class "Default")
      (node (ref "R18") (pin "1") (pinfunction "1_1") (pintype "passive"))
      (node (ref "R22") (pin "2") (pinfunction "2_2") (pintype "passive"))
      (node (ref "XMC1") (pin "34") (pinfunction "P14.0_34") (pintype "input"))
    )
    (net (code "33") (name "/iso_ENA_UH") (class "Default")
      (node (ref "P1") (pin "7") (pinfunction "7_7") (pintype "passive"))
      (node (ref "R9") (pin "1") (pinfunction "1_1") (pintype "passive"))
    )
    (net (code "34") (name "/iso_ENA_UL") (class "Default")
      (node (ref "P6") (pin "7") (pinfunction "7_7") (pintype "passive"))
      (node (ref "R13") (pin "2") (pinfunction "2_2") (pintype "passive"))
    )
    (net (code "35") (name "/iso_ENA_VH") (class "Default")
      (node (ref "P1") (pin "6") (pinfunction "6_6") (pintype "passive"))
      (node (ref "R6") (pin "1") (pinfunction "1_1") (pintype "passive"))
    )
    (net (code "36") (name "/iso_ENA_VL") (class "Default")
      (node (ref "P6") (pin "6") (pinfunction "6_6") (pintype "passive"))
      (node (ref "R12") (pin "1") (pinfunction "1_1") (pintype "passive"))
    )
    (net (code "37") (name "/iso_ENA_WH") (class "Default")
      (node (ref "P1") (pin "5") (pinfunction "5_5") (pintype "passive"))
      (node (ref "R5") (pin "1") (pinfunction "1_1") (pintype "passive"))
    )
    (net (code "38") (name "/iso_ENA_WL") (class "Default")
      (node (ref "P6") (pin "5") (pinfunction "5_5") (pintype "passive"))
      (node (ref "R10") (pin "2") (pinfunction "2_2") (pintype "passive"))
    )
    (net (code "39") (name "/iso_PWM_UH") (class "Default")
      (node (ref "P1") (pin "4") (pinfunction "4_4") (pintype "passive"))
      (node (ref "R42") (pin "2") (pinfunction "2_2") (pintype "passive"))
    )
    (net (code "40") (name "/iso_PWM_UL") (class "Default")
      (node (ref "P6") (pin "4") (pinfunction "4_4") (pintype "passive"))
      (node (ref "R48") (pin "2") (pinfunction "2_2") (pintype "passive"))
    )
    (net (code "41") (name "/iso_PWM_VH") (class "Default")
      (node (ref "P1") (pin "3") (pinfunction "3_3") (pintype "passive"))
      (node (ref "R20") (pin "2") (pinfunction "2_2") (pintype "passive"))
    )
    (net (code "42") (name "/iso_PWM_VL") (class "Default")
      (node (ref "P6") (pin "3") (pinfunction "3_3") (pintype "passive"))
      (node (ref "R34") (pin "2") (pinfunction "2_2") (pintype "passive"))
    )
    (net (code "43") (name "/iso_PWM_WH") (class "Default")
      (node (ref "P1") (pin "2") (pinfunction "2_2") (pintype "passive"))
      (node (ref "R4") (pin "2") (pinfunction "2_2") (pintype "passive"))
    )
    (net (code "44") (name "/iso_PWM_WL") (class "Default")
      (node (ref "P6") (pin "2") (pinfunction "2_2") (pintype "passive"))
      (node (ref "R14") (pin "2") (pinfunction "2_2") (pintype "passive"))
    )
    (net (code "45") (name "/temp") (class "Default")
      (node (ref "P7") (pin "6") (pinfunction "6_6") (pintype "passive"))
      (node (ref "R24") (pin "2") (pinfunction "2_2") (pintype "passive"))
    )
    (net (code "46") (name "/temp_xmc") (class "Default")
      (node (ref "R24") (pin "1") (pinfunction "1_1") (pintype "passive"))
      (node (ref "R27") (pin "2") (pinfunction "2_2") (pintype "passive"))
      (node (ref "XMC1") (pin "12") (pinfunction "P14.13_12") (pintype "input"))
    )
    (net (code "47") (name "/v_dc_xmc") (class "Default")
      (node (ref "R17") (pin "1") (pinfunction "1_1") (pintype "passive"))
      (node (ref "R21") (pin "2") (pinfunction "2_2") (pintype "passive"))
      (node (ref "XMC1") (pin "11") (pinfunction "P14.7_11") (pintype "input"))
    )
    (net (code "48") (name "/vabc_0") (class "Default")
      (node (ref "R26") (pin "1") (pinfunction "1_1") (pintype "passive"))
      (node (ref "R29") (pin "2") (pinfunction "2_2") (pintype "passive"))
      (node (ref "XMC1") (pin "8") (pinfunction "P14.1_8") (pintype "input"))
    )
    (net (code "49") (name "/vabc_1") (class "Default")
      (node (ref "R19") (pin "1") (pinfunction "1_1") (pintype "passive"))
      (node (ref "R23") (pin "2") (pinfunction "2_2") (pintype "passive"))
      (node (ref "XMC1") (pin "9") (pinfunction "P14.3_9") (pintype "input"))
    )
    (net (code "50") (name "/vabc_2") (class "Default")
      (node (ref "R31") (pin "1") (pinfunction "1_1") (pintype "passive"))
      (node (ref "R33") (pin "2") (pinfunction "2_2") (pintype "passive"))
      (node (ref "XMC1") (pin "10") (pinfunction "P14.5_10") (pintype "input"))
    )
    (net (code "51") (name "3V3") (class "Default")
      (node (ref "P7") (pin "1") (pinfunction "1_1") (pintype "passive"))
      (node (ref "P8") (pin "1") (pinfunction "1_1") (pintype "passive"))
      (node (ref "U1") (pin "14") (pinfunction "VCC_14") (pintype "passive"))
      (node (ref "U2") (pin "14") (pinfunction "VCC_14") (pintype "passive"))
      (node (ref "U4") (pin "14") (pinfunction "VCC_14") (pintype "passive"))
    )
    (net (code "52") (name "3V3GND") (class "Default")
      (node (ref "C10") (pin "1") (pinfunction "1_1") (pintype "passive"))
      (node (ref "C12") (pin "1") (pinfunction "1_1") (pintype "passive"))
      (node (ref "C14") (pin "1") (pinfunction "1_1") (pintype "passive"))
      (node (ref "C15") (pin "1") (pinfunction "1_1") (pintype "passive"))
      (node (ref "C4") (pin "1") (pinfunction "1_1") (pintype "passive"))
      (node (ref "C5") (pin "1") (pinfunction "1_1") (pintype "passive"))
      (node (ref "P1") (pin "1") (pinfunction "1_1") (pintype "passive"))
      (node (ref "P1") (pin "8") (pinfunction "8_8") (pintype "passive"))
      (node (ref "P5") (pin "1") (pinfunction "1_1") (pintype "passive"))
      (node (ref "P5") (pin "2") (pinfunction "2_2") (pintype "passive"))
      (node (ref "P5") (pin "3") (pinfunction "3_3") (pintype "passive"))
      (node (ref "P5") (pin "4") (pinfunction "4_4") (pintype "passive"))
      (node (ref "P5") (pin "5") (pinfunction "5_5") (pintype "passive"))
      (node (ref "P5") (pin "6") (pinfunction "6_6") (pintype "passive"))
      (node (ref "P5") (pin "7") (pinfunction "7_7") (pintype "passive"))
      (node (ref "P5") (pin "8") (pinfunction "8_8") (pintype "passive"))
      (node (ref "P6") (pin "1") (pinfunction "1_1") (pintype "passive"))
      (node (ref "P6") (pin "8") (pinfunction "8_8") (pintype "passive"))
      (node (ref "P7") (pin "8") (pinfunction "8_8") (pintype "passive"))
      (node (ref "P8") (pin "8") (pinfunction "8_8") (pintype "passive"))
      (node (ref "R21") (pin "1") (pinfunction "1_1") (pintype "passive"))
      (node (ref "R22") (pin "1") (pinfunction "1_1") (pintype "passive"))
      (node (ref "R23") (pin "1") (pinfunction "1_1") (pintype "passive"))
      (node (ref "R27") (pin "1") (pinfunction "1_1") (pintype "passive"))
      (node (ref "R28") (pin "1") (pinfunction "1_1") (pintype "passive"))
      (node (ref "R29") (pin "1") (pinfunction "1_1") (pintype "passive"))
      (node (ref "R32") (pin "1") (pinfunction "1_1") (pintype "passive"))
      (node (ref "R33") (pin "1") (pinfunction "1_1") (pintype "passive"))
      (node (ref "U1") (pin "7") (pinfunction "GND_7") (pintype "passive"))
      (node (ref "U2") (pin "7") (pinfunction "GND_7") (pintype "passive"))
      (node (ref "U3") (pin "2") (pinfunction "GND_2") (pintype "passive"))
      (node (ref "U4") (pin "7") (pinfunction "GND_7") (pintype "passive"))
      (node (ref "U5") (pin "5") (pinfunction "GND2_5") (pintype "passive"))
      (node (ref "U5") (pin "6") (pinfunction "Out-_6") (pintype "passive"))
      (node (ref "U6") (pin "2") (pinfunction "GND_2") (pintype "passive"))
      (node (ref "U7") (pin "2") (pinfunction "GND_2") (pintype "passive"))
      (node (ref "U8") (pin "5") (pinfunction "GND2_5") (pintype "passive"))
      (node (ref "U8") (pin "6") (pinfunction "Out-_6") (pintype "passive"))
      (node (ref "U9") (pin "5") (pinfunction "GND2_5") (pintype "passive"))
      (node (ref "U9") (pin "6") (pinfunction "Out-_6") (pintype "passive"))
      (node (ref "XMC1") (pin "1") (pinfunction "GND_1") (pintype "power_in"))
      (node (ref "XMC1") (pin "2") (pinfunction "GND_2") (pintype "power_in"))
      (node (ref "XMC1") (pin "3") (pinfunction "GND_3") (pintype "power_in"))
      (node (ref "XMC1") (pin "39") (pinfunction "GND_39") (pintype "power_in"))
      (node (ref "XMC1") (pin "40") (pinfunction "GND_40") (pintype "power_in"))
      (node (ref "XMC1") (pin "41") (pinfunction "GND_41") (pintype "power_in"))
      (node (ref "XMC1") (pin "42") (pinfunction "GND_42") (pintype "power_in"))
      (node (ref "XMC1") (pin "58") (pinfunction "GND_58") (pintype "input"))
      (node (ref "XMC1") (pin "63") (pinfunction "GND_63") (pintype "input"))
      (node (ref "XMC1") (pin "79") (pinfunction "GND_79") (pintype "power_in"))
      (node (ref "XMC1") (pin "80") (pinfunction "GND_80") (pintype "power_in"))
    )
    (net (code "53") (name "5V") (class "Default")
      (node (ref "C10") (pin "2") (pinfunction "2_2") (pintype "passive"))
      (node (ref "C15") (pin "2") (pinfunction "2_2") (pintype "passive"))
      (node (ref "C5") (pin "2") (pinfunction "2_2") (pintype "passive"))
      (node (ref "P7") (pin "2") (pinfunction "2_2") (pintype "passive"))
      (node (ref "P8") (pin "2") (pinfunction "2_2") (pintype "passive"))
      (node (ref "U3") (pin "1") (pinfunction "Vin_1") (pintype "passive"))
      (node (ref "U5") (pin "8") (pinfunction "VDD2_8") (pintype "passive"))
      (node (ref "U6") (pin "1") (pinfunction "Vin_1") (pintype "passive"))
      (node (ref "U7") (pin "1") (pinfunction "Vin_1") (pintype "passive"))
      (node (ref "U8") (pin "8") (pinfunction "VDD2_8") (pintype "passive"))
      (node (ref "U9") (pin "8") (pinfunction "VDD2_8") (pintype "passive"))
      (node (ref "XMC1") (pin "20") (pinfunction "VDD5_20") (pintype "power_in"))
      (node (ref "XMC1") (pin "21") (pinfunction "VDD5_21") (pintype "power_in"))
      (node (ref "XMC1") (pin "60") (pinfunction "VDD5_60") (pintype "power_in"))
      (node (ref "XMC1") (pin "61") (pinfunction "VDD5_61") (pintype "power_in"))
    )
    (net (code "54") (name "Net-(P4-Pad1)") (class "Default")
      (node (ref "P4") (pin "1") (pinfunction "1_1") (pintype "passive"))
      (node (ref "P4") (pin "8") (pinfunction "8_8") (pintype "passive"))
      (node (ref "XMC1") (pin "22") (pinfunction "VDD3.3_22") (pintype "power_in"))
    )
    (net (code "55") (name "Net-(P9-Pad1)") (class "Default")
      (node (ref "P9") (pin "1") (pinfunction "1_1") (pintype "passive"))
      (node (ref "R43") (pin "1") (pinfunction "1_1") (pintype "passive"))
    )
    (net (code "56") (name "Net-(P9-Pad2)") (class "Default")
      (node (ref "P9") (pin "2") (pinfunction "2_2") (pintype "passive"))
      (node (ref "R37") (pin "1") (pinfunction "1_1") (pintype "passive"))
    )
    (net (code "57") (name "Net-(P10-Pad1)") (class "Default")
      (node (ref "P10") (pin "1") (pinfunction "1_1") (pintype "passive"))
      (node (ref "R63") (pin "1") (pinfunction "1_1") (pintype "passive"))
    )
    (net (code "58") (name "Net-(P10-Pad2)") (class "Default")
      (node (ref "P10") (pin "2") (pinfunction "2_2") (pintype "passive"))
      (node (ref "R53") (pin "1") (pinfunction "1_1") (pintype "passive"))
    )
    (net (code "59") (name "Net-(P11-Pad1)") (class "Default")
      (node (ref "P11") (pin "1") (pinfunction "1_1") (pintype "passive"))
      (node (ref "R68") (pin "1") (pinfunction "1_1") (pintype "passive"))
    )
    (net (code "60") (name "Net-(P11-Pad2)") (class "Default")
      (node (ref "P11") (pin "2") (pinfunction "2_2") (pintype "passive"))
      (node (ref "R58") (pin "1") (pinfunction "1_1") (pintype "passive"))
    )
    (net (code "61") (name "Net-(R37-Pad2)") (class "Default")
      (node (ref "R37") (pin "2") (pinfunction "2_2") (pintype "passive"))
      (node (ref "R38") (pin "1") (pinfunction "1_1") (pintype "passive"))
    )
    (net (code "62") (name "Net-(R38-Pad2)") (class "Default")
      (node (ref "R38") (pin "2") (pinfunction "2_2") (pintype "passive"))
      (node (ref "R39") (pin "1") (pinfunction "1_1") (pintype "passive"))
    )
    (net (code "63") (name "Net-(R39-Pad2)") (class "Default")
      (node (ref "R39") (pin "2") (pinfunction "2_2") (pintype "passive"))
      (node (ref "R40") (pin "1") (pinfunction "1_1") (pintype "passive"))
    )
    (net (code "64") (name "Net-(R40-Pad2)") (class "Default")
      (node (ref "R40") (pin "2") (pinfunction "2_2") (pintype "passive"))
      (node (ref "R41") (pin "1") (pinfunction "1_1") (pintype "passive"))
    )
    (net (code "65") (name "Net-(R43-Pad2)") (class "Default")
      (node (ref "R43") (pin "2") (pinfunction "2_2") (pintype "passive"))
      (node (ref "R44") (pin "1") (pinfunction "1_1") (pintype "passive"))
    )
    (net (code "66") (name "Net-(R44-Pad2)") (class "Default")
      (node (ref "R44") (pin "2") (pinfunction "2_2") (pintype "passive"))
      (node (ref "R45") (pin "1") (pinfunction "1_1") (pintype "passive"))
    )
    (net (code "67") (name "Net-(R45-Pad2)") (class "Default")
      (node (ref "R45") (pin "2") (pinfunction "2_2") (pintype "passive"))
      (node (ref "R46") (pin "1") (pinfunction "1_1") (pintype "passive"))
    )
    (net (code "68") (name "Net-(R46-Pad2)") (class "Default")
      (node (ref "R46") (pin "2") (pinfunction "2_2") (pintype "passive"))
      (node (ref "R47") (pin "1") (pinfunction "1_1") (pintype "passive"))
    )
    (net (code "69") (name "Net-(R53-Pad2)") (class "Default")
      (node (ref "R53") (pin "2") (pinfunction "2_2") (pintype "passive"))
      (node (ref "R54") (pin "1") (pinfunction "1_1") (pintype "passive"))
    )
    (net (code "70") (name "Net-(R54-Pad2)") (class "Default")
      (node (ref "R54") (pin "2") (pinfunction "2_2") (pintype "passive"))
      (node (ref "R55") (pin "1") (pinfunction "1_1") (pintype "passive"))
    )
    (net (code "71") (name "Net-(R55-Pad2)") (class "Default")
      (node (ref "R55") (pin "2") (pinfunction "2_2") (pintype "passive"))
      (node (ref "R56") (pin "1") (pinfunction "1_1") (pintype "passive"))
    )
    (net (code "72") (name "Net-(R56-Pad2)") (class "Default")
      (node (ref "R56") (pin "2") (pinfunction "2_2") (pintype "passive"))
      (node (ref "R57") (pin "1") (pinfunction "1_1") (pintype "passive"))
    )
    (net (code "73") (name "Net-(R58-Pad2)") (class "Default")
      (node (ref "R58") (pin "2") (pinfunction "2_2") (pintype "passive"))
      (node (ref "R59") (pin "1") (pinfunction "1_1") (pintype "passive"))
    )
    (net (code "74") (name "Net-(R59-Pad2)") (class "Default")
      (node (ref "R59") (pin "2") (pinfunction "2_2") (pintype "passive"))
      (node (ref "R60") (pin "1") (pinfunction "1_1") (pintype "passive"))
    )
    (net (code "75") (name "Net-(R60-Pad2)") (class "Default")
      (node (ref "R60") (pin "2") (pinfunction "2_2") (pintype "passive"))
      (node (ref "R61") (pin "1") (pinfunction "1_1") (pintype "passive"))
    )
    (net (code "76") (name "Net-(R61-Pad2)") (class "Default")
      (node (ref "R61") (pin "2") (pinfunction "2_2") (pintype "passive"))
      (node (ref "R62") (pin "1") (pinfunction "1_1") (pintype "passive"))
    )
    (net (code "77") (name "Net-(R63-Pad2)") (class "Default")
      (node (ref "R63") (pin "2") (pinfunction "2_2") (pintype "passive"))
      (node (ref "R64") (pin "1") (pinfunction "1_1") (pintype "passive"))
    )
    (net (code "78") (name "Net-(R64-Pad2)") (class "Default")
      (node (ref "R64") (pin "2") (pinfunction "2_2") (pintype "passive"))
      (node (ref "R65") (pin "1") (pinfunction "1_1") (pintype "passive"))
    )
    (net (code "79") (name "Net-(R65-Pad2)") (class "Default")
      (node (ref "R65") (pin "2") (pinfunction "2_2") (pintype "passive"))
      (node (ref "R66") (pin "1") (pinfunction "1_1") (pintype "passive"))
    )
    (net (code "80") (name "Net-(R66-Pad2)") (class "Default")
      (node (ref "R66") (pin "2") (pinfunction "2_2") (pintype "passive"))
      (node (ref "R67") (pin "1") (pinfunction "1_1") (pintype "passive"))
    )
    (net (code "81") (name "Net-(R68-Pad2)") (class "Default")
      (node (ref "R68") (pin "2") (pinfunction "2_2") (pintype "passive"))
      (node (ref "R69") (pin "1") (pinfunction "1_1") (pintype "passive"))
    )
    (net (code "82") (name "Net-(R69-Pad2)") (class "Default")
      (node (ref "R69") (pin "2") (pinfunction "2_2") (pintype "passive"))
      (node (ref "R70") (pin "1") (pinfunction "1_1") (pintype "passive"))
    )
    (net (code "83") (name "Net-(R70-Pad2)") (class "Default")
      (node (ref "R70") (pin "2") (pinfunction "2_2") (pintype "passive"))
      (node (ref "R71") (pin "1") (pinfunction "1_1") (pintype "passive"))
    )
    (net (code "84") (name "Net-(R71-Pad2)") (class "Default")
      (node (ref "R71") (pin "2") (pinfunction "2_2") (pintype "passive"))
      (node (ref "R72") (pin "1") (pinfunction "1_1") (pintype "passive"))
    )
    (net (code "85") (name "Net-(U1-1Y)") (class "Default")
      (node (ref "U1") (pin "3") (pinfunction "1Y_3") (pintype "passive"))
      (node (ref "U1") (pin "5") (pinfunction "2A_5") (pintype "passive"))
      (node (ref "U1") (pin "6") (pinfunction "2B_6") (pintype "passive"))
      (node (ref "U1") (pin "8") (pinfunction "3A_8") (pintype "passive"))
    )
    (net (code "86") (name "Net-(U1-2Y)") (class "Default")
      (node (ref "R4") (pin "1") (pinfunction "1_1") (pintype "passive"))
      (node (ref "U1") (pin "4") (pinfunction "2Y_4") (pintype "passive"))
    )
    (net (code "87") (name "Net-(U1-3Y)") (class "Default")
      (node (ref "U1") (pin "10") (pinfunction "3Y_10") (pintype "passive"))
      (node (ref "U1") (pin "12") (pinfunction "4A_12") (pintype "passive"))
      (node (ref "U1") (pin "13") (pinfunction "4B_13") (pintype "passive"))
    )
    (net (code "88") (name "Net-(U1-4Y)") (class "Default")
      (node (ref "R14") (pin "1") (pinfunction "1_1") (pintype "passive"))
      (node (ref "U1") (pin "11") (pinfunction "4Y_11") (pintype "passive"))
    )
    (net (code "89") (name "Net-(U2-1Y)") (class "Default")
      (node (ref "U2") (pin "3") (pinfunction "1Y_3") (pintype "passive"))
      (node (ref "U2") (pin "5") (pinfunction "2A_5") (pintype "passive"))
      (node (ref "U2") (pin "6") (pinfunction "2B_6") (pintype "passive"))
      (node (ref "U2") (pin "8") (pinfunction "3A_8") (pintype "passive"))
    )
    (net (code "90") (name "Net-(U2-2Y)") (class "Default")
      (node (ref "R20") (pin "1") (pinfunction "1_1") (pintype "passive"))
      (node (ref "U2") (pin "4") (pinfunction "2Y_4") (pintype "passive"))
    )
    (net (code "91") (name "Net-(U2-3Y)") (class "Default")
      (node (ref "U2") (pin "10") (pinfunction "3Y_10") (pintype "passive"))
      (node (ref "U2") (pin "12") (pinfunction "4A_12") (pintype "passive"))
      (node (ref "U2") (pin "13") (pinfunction "4B_13") (pintype "passive"))
    )
    (net (code "92") (name "Net-(U2-4Y)") (class "Default")
      (node (ref "R34") (pin "1") (pinfunction "1_1") (pintype "passive"))
      (node (ref "U2") (pin "11") (pinfunction "4Y_11") (pintype "passive"))
    )
    (net (code "93") (name "Net-(U4-1Y)") (class "Default")
      (node (ref "U4") (pin "3") (pinfunction "1Y_3") (pintype "passive"))
      (node (ref "U4") (pin "5") (pinfunction "2A_5") (pintype "passive"))
      (node (ref "U4") (pin "6") (pinfunction "2B_6") (pintype "passive"))
      (node (ref "U4") (pin "8") (pinfunction "3A_8") (pintype "passive"))
    )
    (net (code "94") (name "Net-(U4-2Y)") (class "Default")
      (node (ref "R42") (pin "1") (pinfunction "1_1") (pintype "passive"))
      (node (ref "U4") (pin "4") (pinfunction "2Y_4") (pintype "passive"))
    )
    (net (code "95") (name "Net-(U4-3Y)") (class "Default")
      (node (ref "U4") (pin "10") (pinfunction "3Y_10") (pintype "passive"))
      (node (ref "U4") (pin "12") (pinfunction "4A_12") (pintype "passive"))
      (node (ref "U4") (pin "13") (pinfunction "4B_13") (pintype "passive"))
    )
    (net (code "96") (name "Net-(U4-4Y)") (class "Default")
      (node (ref "R48") (pin "1") (pinfunction "1_1") (pintype "passive"))
      (node (ref "U4") (pin "11") (pinfunction "4Y_11") (pintype "passive"))
    )
    (net (code "97") (name "Net-(U5-Out+)") (class "Default")
      (node (ref "R35") (pin "1") (pinfunction "1_1") (pintype "passive"))
      (node (ref "U5") (pin "7") (pinfunction "Out+_7") (pintype "passive"))
    )
    (net (code "98") (name "Net-(U8-Out+)") (class "Default")
      (node (ref "R49") (pin "1") (pinfunction "1_1") (pintype "passive"))
      (node (ref "U8") (pin "7") (pinfunction "Out+_7") (pintype "passive"))
    )
    (net (code "99") (name "Net-(U9-Out+)") (class "Default")
      (node (ref "R50") (pin "1") (pinfunction "1_1") (pintype "passive"))
      (node (ref "U9") (pin "7") (pinfunction "Out+_7") (pintype "passive"))
    )
    (net (code "100") (name "Net-(XMC1A-P0.2)") (class "Default")
      (node (ref "R9") (pin "2") (pinfunction "2_2") (pintype "passive"))
      (node (ref "XMC1") (pin "65") (pinfunction "P0.2_65") (pintype "input"))
    )
    (net (code "101") (name "Net-(XMC1A-P0.4)") (class "Default")
      (node (ref "R11") (pin "1") (pinfunction "1_1") (pintype "passive"))
      (node (ref "XMC1") (pin "64") (pinfunction "P0.4_64") (pintype "input"))
    )
    (net (code "102") (name "Net-(XMC1A-P0.5)") (class "Default")
      (node (ref "R8") (pin "2") (pinfunction "2_2") (pintype "passive"))
      (node (ref "XMC1") (pin "56") (pinfunction "P0.5_56") (pintype "input"))
    )
    (net (code "103") (name "Net-(XMC1A-P0.6)") (class "Default")
      (node (ref "R7") (pin "1") (pinfunction "1_1") (pintype "passive"))
      (node (ref "XMC1") (pin "66") (pinfunction "P0.6_66") (pintype "input"))
    )
    (net (code "104") (name "Net-(XMC1A-P0.7)") (class "Default")
      (node (ref "P2") (pin "8") (pinfunction "8_8") (pintype "passive"))
      (node (ref "XMC1") (pin "53") (pinfunction "P0.7_53") (pintype "input"))
    )
    (net (code "105") (name "Net-(XMC1A-P0.8)") (class "Default")
      (node (ref "P3") (pin "7") (pinfunction "7_7") (pintype "passive"))
      (node (ref "XMC1") (pin "69") (pinfunction "P0.8_69") (pintype "input"))
    )
    (net (code "106") (name "Net-(XMC1A-P0.11)") (class "Default")
      (node (ref "R6") (pin "2") (pinfunction "2_2") (pintype "passive"))
      (node (ref "XMC1") (pin "55") (pinfunction "P0.11_55") (pintype "input"))
    )
    (net (code "107") (name "Net-(XMC1A-P1.0)") (class "Default")
      (node (ref "P2") (pin "6") (pinfunction "6_6") (pintype "passive"))
      (node (ref "XMC1") (pin "51") (pinfunction "P1.0_51") (pintype "input"))
    )
    (net (code "108") (name "Net-(XMC1A-P1.1)") (class "Default")
      (node (ref "P3") (pin "5") (pinfunction "5_5") (pintype "passive"))
      (node (ref "XMC1") (pin "71") (pinfunction "P1.1_71") (pintype "input"))
    )
    (net (code "109") (name "Net-(XMC1A-P1.3)") (class "Default")
      (node (ref "P3") (pin "4") (pinfunction "4_4") (pintype "passive"))
      (node (ref "XMC1") (pin "72") (pinfunction "P1.3_72") (pintype "input"))
    )
    (net (code "110") (name "Net-(XMC1A-P1.4)") (class "Default")
      (node (ref "P2") (pin "4") (pinfunction "4_4") (pintype "passive"))
      (node (ref "XMC1") (pin "49") (pinfunction "P1.4_49") (pintype "input"))
    )
    (net (code "111") (name "Net-(XMC1A-P1.5)") (class "Default")
      (node (ref "P3") (pin "3") (pinfunction "3_3") (pintype "passive"))
      (node (ref "XMC1") (pin "73") (pinfunction "P1.5_73") (pintype "input"))
    )
    (net (code "112") (name "Net-(XMC1A-P1.8)") (class "Default")
      (node (ref "P2") (pin "7") (pinfunction "7_7") (pintype "passive"))
      (node (ref "XMC1") (pin "52") (pinfunction "P1.8_52") (pintype "input"))
    )
    (net (code "113") (name "Net-(XMC1A-P1.9)") (class "Default")
      (node (ref "P3") (pin "6") (pinfunction "6_6") (pintype "passive"))
      (node (ref "XMC1") (pin "70") (pinfunction "P1.9_70") (pintype "input"))
    )
    (net (code "114") (name "Net-(XMC1A-P1.10)") (class "Default")
      (node (ref "P2") (pin "3") (pinfunction "3_3") (pintype "passive"))
      (node (ref "XMC1") (pin "48") (pinfunction "P1.10_48") (pintype "input"))
    )
    (net (code "115") (name "Net-(XMC1A-P1.11)") (class "Default")
      (node (ref "P3") (pin "2") (pinfunction "2_2") (pintype "passive"))
      (node (ref "XMC1") (pin "74") (pinfunction "P1.11_74") (pintype "input"))
    )
    (net (code "116") (name "Net-(XMC1A-P1.12)") (class "Default")
      (node (ref "P2") (pin "2") (pinfunction "2_2") (pintype "passive"))
      (node (ref "XMC1") (pin "47") (pinfunction "P1.12_47") (pintype "input"))
    )
    (net (code "117") (name "Net-(XMC1A-P1.13)") (class "Default")
      (node (ref "P3") (pin "1") (pinfunction "1_1") (pintype "passive"))
      (node (ref "XMC1") (pin "75") (pinfunction "P1.13_75") (pintype "input"))
    )
    (net (code "118") (name "Net-(XMC1A-P1.14)") (class "Default")
      (node (ref "P2") (pin "1") (pinfunction "1_1") (pintype "passive"))
      (node (ref "XMC1") (pin "46") (pinfunction "P1.14_46") (pintype "input"))
    )
    (net (code "119") (name "Net-(XMC1A-P2.6)") (class "Default")
      (node (ref "R1") (pin "2") (pinfunction "2_2") (pintype "passive"))
      (node (ref "XMC1") (pin "43") (pinfunction "P2.6_43") (pintype "power_in"))
    )
    (net (code "120") (name "Net-(XMC1A-P3.3)") (class "Default")
      (node (ref "R5") (pin "2") (pinfunction "2_2") (pintype "passive"))
      (node (ref "XMC1") (pin "54") (pinfunction "P3.3_54") (pintype "input"))
    )
    (net (code "121") (name "Net-(XMC1A-P3.4)") (class "Default")
      (node (ref "P3") (pin "8") (pinfunction "8_8") (pintype "passive"))
      (node (ref "XMC1") (pin "68") (pinfunction "P3.4_68") (pintype "input"))
    )
    (net (code "122") (name "Net-(XMC1A-P5.0)") (class "Default")
      (node (ref "R3") (pin "2") (pinfunction "2_2") (pintype "passive"))
      (node (ref "XMC1") (pin "45") (pinfunction "P5.0_45") (pintype "input"))
    )
    (net (code "123") (name "Net-(XMC1A-P5.2)") (class "Default")
      (node (ref "R2") (pin "2") (pinfunction "2_2") (pintype "passive"))
      (node (ref "XMC1") (pin "44") (pinfunction "P5.2_44") (pintype "input"))
    )
    (net (code "124") (name "Net-(XMC1B-P0.0)") (class "Default")
      (node (ref "R16") (pin "1") (pinfunction "1_1") (pintype "passive"))
      (node (ref "XMC1") (pin "23") (pinfunction "P0.0_23") (pintype "input"))
    )
    (net (code "125") (name "Net-(XMC1B-P0.1)") (class "Default")
      (node (ref "R15") (pin "1") (pinfunction "1_1") (pintype "passive"))
      (node (ref "XMC1") (pin "24") (pinfunction "P0.1_24") (pintype "input"))
    )
    (net (code "126") (name "Net-(XMC1B-P3.0)") (class "Default")
      (node (ref "R10") (pin "1") (pinfunction "1_1") (pintype "passive"))
      (node (ref "XMC1") (pin "26") (pinfunction "P3.0_26") (pintype "input"))
    )
    (net (code "127") (name "Net-(XMC1B-P3.1)") (class "Default")
      (node (ref "R12") (pin "2") (pinfunction "2_2") (pintype "passive"))
      (node (ref "XMC1") (pin "16") (pinfunction "P3.1_16") (pintype "input"))
    )
    (net (code "128") (name "Net-(XMC1B-P3.2)") (class "Default")
      (node (ref "R13") (pin "1") (pinfunction "1_1") (pintype "passive"))
      (node (ref "XMC1") (pin "25") (pinfunction "P3.2_25") (pintype "input"))
    )
    (net (code "129") (name "Net-(XMC1B-P14.4)") (class "Default")
      (node (ref "P4") (pin "3") (pinfunction "3_3") (pintype "passive"))
      (node (ref "XMC1") (pin "32") (pinfunction "P14.4_32") (pintype "input"))
    )
    (net (code "130") (name "Net-(XMC1B-P14.6)") (class "Default")
      (node (ref "P4") (pin "4") (pinfunction "4_4") (pintype "passive"))
      (node (ref "XMC1") (pin "31") (pinfunction "P14.6_31") (pintype "input"))
    )
    (net (code "131") (name "Net-(XMC1B-P14.12)") (class "Default")
      (node (ref "P4") (pin "5") (pinfunction "5_5") (pintype "passive"))
      (node (ref "XMC1") (pin "30") (pinfunction "P14.12_30") (pintype "input"))
    )
    (net (code "132") (name "Net-(XMC1B-P14.14)") (class "Default")
      (node (ref "P4") (pin "6") (pinfunction "6_6") (pintype "passive"))
      (node (ref "XMC1") (pin "29") (pinfunction "P14.14_29") (pintype "input"))
    )
    (net (code "133") (name "Net-(XMC1B-P15.2)") (class "Default")
      (node (ref "P4") (pin "7") (pinfunction "7_7") (pintype "passive"))
      (node (ref "XMC1") (pin "28") (pinfunction "P15.2_28") (pintype "input"))
    )
    (net (code "134") (name "unconnected-(P7-Pad5)") (class "Default")
      (node (ref "P7") (pin "5") (pinfunction "5_5") (pintype "passive+no_connect"))
    )
    (net (code "135") (name "unconnected-(XMC1A-P0.3-Pad57)") (class "Default")
      (node (ref "XMC1") (pin "57") (pinfunction "P0.3_57") (pintype "input"))
    )
    (net (code "136") (name "unconnected-(XMC1A-P0.12-Pad67)") (class "Default")
      (node (ref "XMC1") (pin "67") (pinfunction "P0.12_67") (pintype "input"))
    )
    (net (code "137") (name "unconnected-(XMC1A-P1.15-Pad76)") (class "Default")
      (node (ref "XMC1") (pin "76") (pinfunction "P1.15_76") (pintype "input"))
    )
    (net (code "138") (name "unconnected-(XMC1A-P5.1-Pad77)") (class "Default")
      (node (ref "XMC1") (pin "77") (pinfunction "P5.1_77") (pintype "input"))
    )
    (net (code "139") (name "unconnected-(XMC1A-P5.7-Pad78)") (class "Default")
      (node (ref "XMC1") (pin "78") (pinfunction "P5.7_78") (pintype "input"))
    )
    (net (code "140") (name "unconnected-(XMC1A-VDD3.3-Pad59)") (class "Default")
      (node (ref "XMC1") (pin "59") (pinfunction "VDD3.3_59") (pintype "power_in"))
    )
    (net (code "141") (name "unconnected-(XMC1A-VDD3.3-Pad62)") (class "Default")
      (node (ref "XMC1") (pin "62") (pinfunction "VDD3.3_62") (pintype "power_in"))
    )
    (net (code "142") (name "unconnected-(XMC1B-HIB_0-Pad27)") (class "Default")
      (node (ref "XMC1") (pin "27") (pinfunction "HIB_0_27") (pintype "input"))
    )
    (net (code "143") (name "unconnected-(XMC1B-HIB_1-Pad15)") (class "Default")
      (node (ref "XMC1") (pin "15") (pinfunction "HIB_1_15") (pintype "input"))
    )
    (net (code "144") (name "unconnected-(XMC1B-P0.9-Pad17)") (class "Default")
      (node (ref "XMC1") (pin "17") (pinfunction "P0.9_17") (pintype "input"))
    )
    (net (code "145") (name "unconnected-(XMC1B-P2.1-Pad4)") (class "Default")
      (node (ref "XMC1") (pin "4") (pinfunction "P2.1_4") (pintype "input"))
    )
    (net (code "146") (name "unconnected-(XMC1B-P2.10-Pad37)") (class "Default")
      (node (ref "XMC1") (pin "37") (pinfunction "P2.10_37") (pintype "input"))
    )
    (net (code "147") (name "unconnected-(XMC1B-P2.14-Pad5)") (class "Default")
      (node (ref "XMC1") (pin "5") (pinfunction "P2.14_5") (pintype "input"))
    )
    (net (code "148") (name "unconnected-(XMC1B-P2.15-Pad6)") (class "Default")
      (node (ref "XMC1") (pin "6") (pinfunction "P2.15_6") (pintype "input"))
    )
    (net (code "149") (name "unconnected-(XMC1B-P14.9-Pad35)") (class "Default")
      (node (ref "XMC1") (pin "35") (pinfunction "P14.9_35") (pintype "input"))
    )
    (net (code "150") (name "unconnected-(XMC1B-P14.15-Pad13)") (class "Default")
      (node (ref "XMC1") (pin "13") (pinfunction "P14.15_13") (pintype "input"))
    )
    (net (code "151") (name "unconnected-(XMC1B-P15.3-Pad14)") (class "Default")
      (node (ref "XMC1") (pin "14") (pinfunction "P15.3_14") (pintype "input"))
    )
    (net (code "152") (name "unconnected-(XMC1B-RST-Pad38)") (class "Default")
      (node (ref "XMC1") (pin "38") (pinfunction "RST_38") (pintype "input"))
    )
    (net (code "153") (name "unconnected-(XMC1B-VAREF-Pad7)") (class "Default")
      (node (ref "XMC1") (pin "7") (pinfunction "VAREF_7") (pintype "input"))
    )
    (net (code "154") (name "unconnected-(XMC1B-VDD3.3-Pad19)") (class "Default")
      (node (ref "XMC1") (pin "19") (pinfunction "VDD3.3_19") (pintype "power_in"))
    )
  )
)
